# Wireless_RIFID_Reader.net
KiCad netlist of a schematic drawn in EAGLE
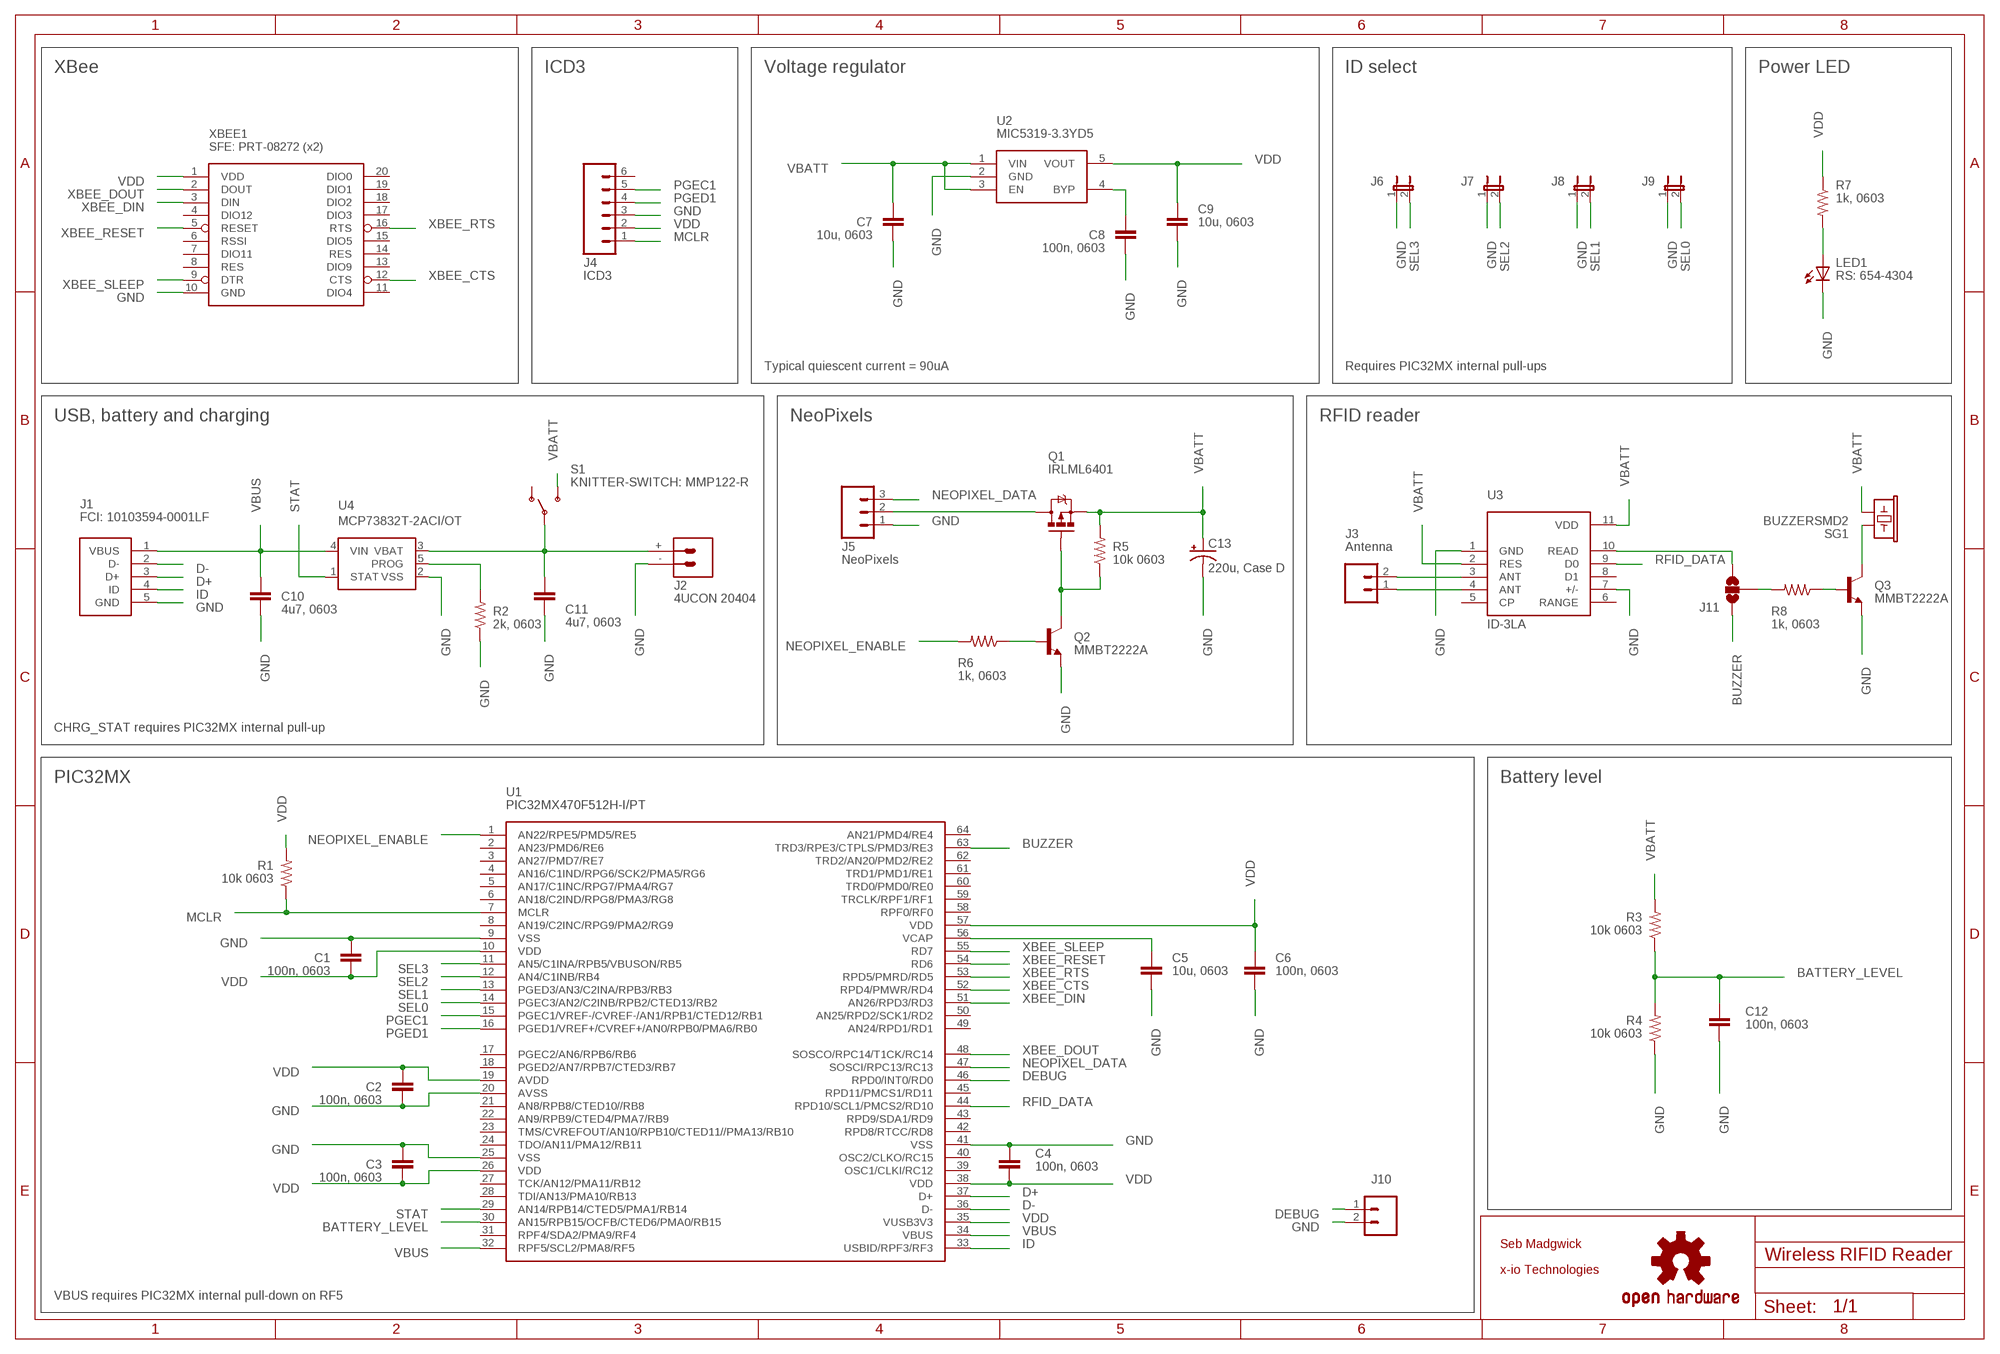
[diagram p0: schematic, sheet 1]

(export (version "E")
  (design (tool "Eeschema 10.0.6"))
  (components
    (comp (ref "C1")
      (value "100n, 0603")
      (footprint "eagle-import:0402-CAP")
      (libsource (lib "eagle-import") (part "CAP0402-CAP"))
    )
    (comp (ref "C2")
      (value "100n, 0603")
      (footprint "eagle-import:0402-CAP")
      (libsource (lib "eagle-import") (part "CAP0402-CAP"))
    )
    (comp (ref "C3")
      (value "100n, 0603")
      (footprint "eagle-import:0402-CAP")
      (libsource (lib "eagle-import") (part "CAP0402-CAP"))
    )
    (comp (ref "C4")
      (value "100n, 0603")
      (footprint "eagle-import:0402-CAP")
      (libsource (lib "eagle-import") (part "CAP0402-CAP"))
    )
    (comp (ref "C5")
      (value "10u, 0603")
      (footprint "eagle-import:0402-CAP")
      (libsource (lib "eagle-import") (part "CAP0402-CAP"))
    )
    (comp (ref "C6")
      (value "100n, 0603")
      (footprint "eagle-import:0402-CAP")
      (libsource (lib "eagle-import") (part "CAP0402-CAP"))
    )
    (comp (ref "C7")
      (value "10u, 0603")
      (footprint "eagle-import:0402-CAP")
      (libsource (lib "eagle-import") (part "CAP0402-CAP"))
    )
    (comp (ref "C8")
      (value "100n, 0603")
      (footprint "eagle-import:0402-CAP")
      (libsource (lib "eagle-import") (part "CAP0402-CAP"))
    )
    (comp (ref "C9")
      (value "10u, 0603")
      (footprint "eagle-import:0402-CAP")
      (libsource (lib "eagle-import") (part "CAP0402-CAP"))
    )
    (comp (ref "C10")
      (value "4u7, 0603")
      (footprint "eagle-import:0402-CAP")
      (libsource (lib "eagle-import") (part "CAP0402-CAP"))
    )
    (comp (ref "C11")
      (value "4u7, 0603")
      (footprint "eagle-import:0402-CAP")
      (libsource (lib "eagle-import") (part "CAP0402-CAP"))
    )
    (comp (ref "C12")
      (value "100n, 0603")
      (footprint "eagle-import:0402-CAP")
      (libsource (lib "eagle-import") (part "CAP0402-CAP"))
    )
    (comp (ref "C13")
      (value "220u, Case D")
      (footprint "eagle-import:SMC_D")
      (libsource (lib "eagle-import") (part "CPOL-USSMCD"))
    )
    (comp (ref "J1")
      (value "FCI: 10103594-0001LF")
      (footprint "eagle-import:10103594-0001LF")
      (libsource (lib "eagle-import") (part "USB-MICRO-B"))
    )
    (comp (ref "J2")
      (value "4UCON 20404")
      (footprint "eagle-import:JST-R_A")
      (libsource (lib "eagle-import") (part "JST"))
    )
    (comp (ref "J3")
      (value "Antenna")
      (footprint "eagle-import:1X02")
      (libsource (lib "eagle-import") (part "SparkFun-Connectors_M02PTH"))
    )
    (comp (ref "J4")
      (value "ICD3")
      (footprint "eagle-import:1X06_NO_SILK")
      (libsource (lib "eagle-import") (part "M06NO_SILK"))
    )
    (comp (ref "J5")
      (value "NeoPixels")
      (footprint "eagle-import:1X03")
      (libsource (lib "eagle-import") (part "M03PTH"))
    )
    (comp (ref "J6")
      (value "JUMPER-2SMD-NO")
      (footprint "eagle-import:SJ_2S-NO")
      (libsource (lib "eagle-import") (part "JUMPER-2SMD-NO"))
    )
    (comp (ref "J7")
      (value "JUMPER-2SMD-NO")
      (footprint "eagle-import:SJ_2S-NO")
      (libsource (lib "eagle-import") (part "JUMPER-2SMD-NO"))
    )
    (comp (ref "J8")
      (value "JUMPER-2SMD-NO")
      (footprint "eagle-import:SJ_2S-NO")
      (libsource (lib "eagle-import") (part "JUMPER-2SMD-NO"))
    )
    (comp (ref "J9")
      (value "JUMPER-2SMD-NO")
      (footprint "eagle-import:SJ_2S-NO")
      (libsource (lib "eagle-import") (part "JUMPER-2SMD-NO"))
    )
    (comp (ref "J10")
      (value "M02PTH")
      (footprint "eagle-import:1X02")
      (libsource (lib "eagle-import") (part "M02PTH"))
    )
    (comp (ref "J11")
      (value "JUMPER-PAD-3-NOFULL_BOX_SILK")
      (footprint "eagle-import:PAD-JUMPER-3-NO_YES_SILK_FULL_BOX")
      (libsource (lib "eagle-import") (part "JUMPER-PAD-3-NOFULL_BOX_SILK"))
    )
    (comp (ref "LED1")
      (value "RS: 654-4304")
      (footprint "eagle-import:LED-0603")
      (libsource (lib "eagle-import") (part "LED0603"))
    )
    (comp (ref "LOGO1")
      (value "OSHW-LOGOM")
      (footprint "eagle-import:OSHW-LOGO-M")
      (libsource (lib "eagle-import") (part "OSHW-LOGOM"))
    )
    (comp (ref "Q1")
      (value "IRLML6401")
      (footprint "eagle-import:SOT23")
      (libsource (lib "eagle-import") (part "MOSFET-PCHANNEL"))
    )
    (comp (ref "Q2")
      (value "MMBT2222A")
      (footprint "eagle-import:SOT23-3")
      (libsource (lib "eagle-import") (part "TRANSISTOR_NPNMMBT2222A"))
    )
    (comp (ref "Q3")
      (value "MMBT2222A")
      (footprint "eagle-import:SOT23-3")
      (libsource (lib "eagle-import") (part "TRANSISTOR_NPNMMBT2222A"))
    )
    (comp (ref "R1")
      (value "10k 0603")
      (footprint "eagle-import:0402-RES")
      (libsource (lib "eagle-import") (part "RESISTOR0402-RES"))
    )
    (comp (ref "R2")
      (value "2k, 0603")
      (footprint "eagle-import:0402-RES")
      (libsource (lib "eagle-import") (part "RESISTOR0402-RES"))
    )
    (comp (ref "R3")
      (value "10k 0603")
      (footprint "eagle-import:0402-RES")
      (libsource (lib "eagle-import") (part "RESISTOR0402-RES"))
    )
    (comp (ref "R4")
      (value "10k 0603")
      (footprint "eagle-import:0402-RES")
      (libsource (lib "eagle-import") (part "RESISTOR0402-RES"))
    )
    (comp (ref "R5")
      (value "10k 0603")
      (footprint "eagle-import:0402-RES")
      (libsource (lib "eagle-import") (part "RESISTOR0402-RES"))
    )
    (comp (ref "R6")
      (value "1k, 0603")
      (footprint "eagle-import:0402-RES")
      (libsource (lib "eagle-import") (part "RESISTOR0402-RES"))
    )
    (comp (ref "R7")
      (value "1k, 0603")
      (footprint "eagle-import:0402-RES")
      (libsource (lib "eagle-import") (part "RESISTOR0402-RES"))
    )
    (comp (ref "R8")
      (value "1k, 0603")
      (footprint "eagle-import:0402-RES")
      (libsource (lib "eagle-import") (part "RESISTOR0402-RES"))
    )
    (comp (ref "S1")
      (value "KNITTER-SWITCH: MMP122-R")
      (footprint "eagle-import:MMP122-R")
      (libsource (lib "eagle-import") (part "SWITCH-DPSTMMP122-R"))
    )
    (comp (ref "SG1")
      (value "BUZZERSMD2")
      (footprint "eagle-import:BUZZER-CCV")
      (libsource (lib "eagle-import") (part "BUZZERSMD2"))
    )
    (comp (ref "U1")
      (value "PIC32MX470F512H-I/PT")
      (footprint "eagle-import:TQFP64-10X10")
      (libsource (lib "eagle-import") (part "PIC32MX470F512H-I/PT"))
    )
    (comp (ref "U2")
      (value "MIC5319-3.3YD5")
      (footprint "eagle-import:SOT23-5")
      (libsource (lib "eagle-import") (part "MIC5319"))
    )
    (comp (ref "U3")
      (value "ID-3LA")
      (footprint "eagle-import:ID-3LA")
      (libsource (lib "eagle-import") (part "ID-3LA"))
    )
    (comp (ref "U4")
      (value "MCP73832T-2ACI/OT")
      (footprint "eagle-import:SOT23-5")
      (libsource (lib "eagle-import") (part "MCP73831"))
    )
    (comp (ref "XBEE1")
      (value "SFE: PRT-08272 (x2)")
      (footprint "eagle-import:XBEE-1")
      (libsource (lib "eagle-import") (part "XBEE-1B1"))
    )
  )
  (nets
    (net (code "1") (name "/BATTERY_LEVEL") (class "Default")
      (node (ref "C12") (pin "1") (pinfunction "1_1") (pintype "passive"))
      (node (ref "R3") (pin "1") (pinfunction "1_1") (pintype "passive"))
      (node (ref "R4") (pin "2") (pinfunction "2_2") (pintype "passive"))
      (node (ref "U1") (pin "30") (pinfunction "AN15/RPB15/OCFB/CTED6/PMA0/RB15_30") (pintype "bidirectional"))
    )
    (net (code "2") (name "/BUZZER") (class "Default")
      (node (ref "J11") (pin "1") (pinfunction "1_1") (pintype "passive"))
      (node (ref "U1") (pin "63") (pinfunction "TRD3/RPE3/CTPLS/PMD3/RE3_63") (pintype "bidirectional"))
    )
    (net (code "3") (name "/D+") (class "Default")
      (node (ref "J1") (pin "3") (pinfunction "D+_3") (pintype "bidirectional"))
      (node (ref "U1") (pin "37") (pinfunction "D+_37") (pintype "bidirectional"))
    )
    (net (code "4") (name "/D-") (class "Default")
      (node (ref "J1") (pin "2") (pinfunction "D-_2") (pintype "bidirectional"))
      (node (ref "U1") (pin "36") (pinfunction "D-_36") (pintype "bidirectional"))
    )
    (net (code "5") (name "/DEBUG") (class "Default")
      (node (ref "J10") (pin "1") (pinfunction "1_1") (pintype "passive"))
      (node (ref "U1") (pin "46") (pinfunction "RPD0/INT0/RD0_46") (pintype "bidirectional"))
    )
    (net (code "6") (name "/GND") (class "Default")
      (node (ref "C1") (pin "1") (pinfunction "1_1") (pintype "passive"))
      (node (ref "C10") (pin "2") (pinfunction "2_2") (pintype "passive"))
      (node (ref "C11") (pin "2") (pinfunction "2_2") (pintype "passive"))
      (node (ref "C12") (pin "2") (pinfunction "2_2") (pintype "passive"))
      (node (ref "C13") (pin "-") (pinfunction "-_-") (pintype "passive"))
      (node (ref "C2") (pin "2") (pinfunction "2_2") (pintype "passive"))
      (node (ref "C3") (pin "1") (pinfunction "1_1") (pintype "passive"))
      (node (ref "C4") (pin "1") (pinfunction "1_1") (pintype "passive"))
      (node (ref "C5") (pin "2") (pinfunction "2_2") (pintype "passive"))
      (node (ref "C6") (pin "2") (pinfunction "2_2") (pintype "passive"))
      (node (ref "C7") (pin "2") (pinfunction "2_2") (pintype "passive"))
      (node (ref "C8") (pin "2") (pinfunction "2_2") (pintype "passive"))
      (node (ref "C9") (pin "2") (pinfunction "2_2") (pintype "passive"))
      (node (ref "J1") (pin "5") (pinfunction "GND_5") (pintype "bidirectional"))
      (node (ref "J10") (pin "2") (pinfunction "2_2") (pintype "passive"))
      (node (ref "J2") (pin "-") (pintype "bidirectional"))
      (node (ref "J4") (pin "3") (pinfunction "3_3") (pintype "passive"))
      (node (ref "J5") (pin "1") (pinfunction "1_1") (pintype "passive"))
      (node (ref "J6") (pin "1") (pinfunction "1_1") (pintype "passive"))
      (node (ref "J7") (pin "1") (pinfunction "1_1") (pintype "passive"))
      (node (ref "J8") (pin "1") (pinfunction "1_1") (pintype "passive"))
      (node (ref "J9") (pin "1") (pinfunction "1_1") (pintype "passive"))
      (node (ref "LED1") (pin "C") (pinfunction "C_C") (pintype "passive"))
      (node (ref "Q2") (pin "2") (pinfunction "E_2") (pintype "passive"))
      (node (ref "Q3") (pin "2") (pinfunction "E_2") (pintype "passive"))
      (node (ref "R2") (pin "1") (pinfunction "1_1") (pintype "passive"))
      (node (ref "R4") (pin "1") (pinfunction "1_1") (pintype "passive"))
      (node (ref "U1") (pin "20") (pinfunction "AVSS_20") (pintype "bidirectional"))
      (node (ref "U1") (pin "25") (pinfunction "VSS_25") (pintype "bidirectional"))
      (node (ref "U1") (pin "41") (pinfunction "VSS_41") (pintype "bidirectional"))
      (node (ref "U1") (pin "9") (pinfunction "VSS_9") (pintype "bidirectional"))
      (node (ref "U2") (pin "2") (pinfunction "GND_2") (pintype "bidirectional"))
      (node (ref "U3") (pin "1") (pinfunction "GND_1") (pintype "bidirectional"))
      (node (ref "U3") (pin "7") (pinfunction "+/-_7") (pintype "bidirectional"))
      (node (ref "U4") (pin "2") (pinfunction "VSS_2") (pintype "power_in"))
      (node (ref "XBEE1") (pin "10") (pinfunction "GND_10") (pintype "power_in"))
    )
    (net (code "7") (name "/ID") (class "Default")
      (node (ref "J1") (pin "4") (pinfunction "ID_4") (pintype "bidirectional"))
      (node (ref "U1") (pin "33") (pinfunction "USBID/RPF3/RF3_33") (pintype "bidirectional"))
    )
    (net (code "8") (name "/MCLR") (class "Default")
      (node (ref "J4") (pin "1") (pinfunction "1_1") (pintype "passive"))
      (node (ref "R1") (pin "1") (pinfunction "1_1") (pintype "passive"))
      (node (ref "U1") (pin "7") (pinfunction "MCLR_7") (pintype "bidirectional"))
    )
    (net (code "9") (name "/NEOPIXEL_DATA") (class "Default")
      (node (ref "J5") (pin "3") (pinfunction "3_3") (pintype "passive"))
      (node (ref "U1") (pin "47") (pinfunction "SOSCI/RPC13/RC13_47") (pintype "bidirectional"))
    )
    (net (code "10") (name "/NEOPIXEL_ENABLE") (class "Default")
      (node (ref "R6") (pin "2") (pinfunction "2_2") (pintype "passive"))
      (node (ref "U1") (pin "1") (pinfunction "AN22/RPE5/PMD5/RE5_1") (pintype "bidirectional"))
    )
    (net (code "11") (name "/PGEC1") (class "Default")
      (node (ref "J4") (pin "5") (pinfunction "5_5") (pintype "passive"))
      (node (ref "U1") (pin "15") (pinfunction "PGEC1/VREF-/CVREF-/AN1/RPB1/CTED12/RB1_15") (pintype "bidirectional"))
    )
    (net (code "12") (name "/PGED1") (class "Default")
      (node (ref "J4") (pin "4") (pinfunction "4_4") (pintype "passive"))
      (node (ref "U1") (pin "16") (pinfunction "PGED1/VREF+/CVREF+/AN0/RPB0/PMA6/RB0_16") (pintype "bidirectional"))
    )
    (net (code "13") (name "/RFID_DATA") (class "Default")
      (node (ref "U1") (pin "44") (pinfunction "RPD10/SCL1/PMCS2/RD10_44") (pintype "bidirectional"))
      (node (ref "U3") (pin "9") (pinfunction "D0_9") (pintype "bidirectional"))
    )
    (net (code "14") (name "/SEL0") (class "Default")
      (node (ref "J9") (pin "2") (pinfunction "2_2") (pintype "passive"))
      (node (ref "U1") (pin "14") (pinfunction "PGEC3/AN2/C2INB/RPB2/CTED13/RB2_14") (pintype "bidirectional"))
    )
    (net (code "15") (name "/SEL1") (class "Default")
      (node (ref "J8") (pin "2") (pinfunction "2_2") (pintype "passive"))
      (node (ref "U1") (pin "13") (pinfunction "PGED3/AN3/C2INA/RPB3/RB3_13") (pintype "bidirectional"))
    )
    (net (code "16") (name "/SEL2") (class "Default")
      (node (ref "J7") (pin "2") (pinfunction "2_2") (pintype "passive"))
      (node (ref "U1") (pin "12") (pinfunction "AN4/C1INB/RB4_12") (pintype "bidirectional"))
    )
    (net (code "17") (name "/SEL3") (class "Default")
      (node (ref "J6") (pin "2") (pinfunction "2_2") (pintype "passive"))
      (node (ref "U1") (pin "11") (pinfunction "AN5/C1INA/RPB5/VBUSON/RB5_11") (pintype "bidirectional"))
    )
    (net (code "18") (name "/STAT") (class "Default")
      (node (ref "U1") (pin "29") (pinfunction "AN14/RPB14/CTED5/PMA1/RB14_29") (pintype "bidirectional"))
      (node (ref "U4") (pin "1") (pinfunction "STAT_1") (pintype "output"))
    )
    (net (code "19") (name "/VBATT") (class "Default")
      (node (ref "C13") (pin "+") (pinfunction "+_+") (pintype "passive"))
      (node (ref "C7") (pin "1") (pinfunction "1_1") (pintype "passive"))
      (node (ref "Q1") (pin "2") (pinfunction "S_2") (pintype "passive"))
      (node (ref "R3") (pin "2") (pinfunction "2_2") (pintype "passive"))
      (node (ref "R5") (pin "2") (pinfunction "2_2") (pintype "passive"))
      (node (ref "S1") (pin "3") (pinfunction "3_3") (pintype "passive"))
      (node (ref "SG1") (pin "-") (pinfunction "2_-") (pintype "passive"))
      (node (ref "U2") (pin "1") (pinfunction "VIN_1") (pintype "bidirectional"))
      (node (ref "U2") (pin "3") (pinfunction "EN_3") (pintype "bidirectional"))
      (node (ref "U3") (pin "11") (pinfunction "VDD_11") (pintype "bidirectional"))
      (node (ref "U3") (pin "2") (pinfunction "RES_2") (pintype "bidirectional"))
    )
    (net (code "20") (name "/VBUS") (class "Default")
      (node (ref "C10") (pin "1") (pinfunction "1_1") (pintype "passive"))
      (node (ref "J1") (pin "1") (pinfunction "VBUS_1") (pintype "bidirectional"))
      (node (ref "U1") (pin "32") (pinfunction "RPF5/SCL2/PMA8/RF5_32") (pintype "bidirectional"))
      (node (ref "U1") (pin "34") (pinfunction "VBUS_34") (pintype "bidirectional"))
      (node (ref "U4") (pin "4") (pinfunction "VIN_4") (pintype "power_in"))
    )
    (net (code "21") (name "/VDD") (class "Default")
      (node (ref "C1") (pin "2") (pinfunction "2_2") (pintype "passive"))
      (node (ref "C2") (pin "1") (pinfunction "1_1") (pintype "passive"))
      (node (ref "C3") (pin "2") (pinfunction "2_2") (pintype "passive"))
      (node (ref "C4") (pin "2") (pinfunction "2_2") (pintype "passive"))
      (node (ref "C6") (pin "1") (pinfunction "1_1") (pintype "passive"))
      (node (ref "C9") (pin "1") (pinfunction "1_1") (pintype "passive"))
      (node (ref "J4") (pin "2") (pinfunction "2_2") (pintype "passive"))
      (node (ref "R1") (pin "2") (pinfunction "2_2") (pintype "passive"))
      (node (ref "R7") (pin "1") (pinfunction "1_1") (pintype "passive"))
      (node (ref "U1") (pin "10") (pinfunction "VDD_10") (pintype "bidirectional"))
      (node (ref "U1") (pin "19") (pinfunction "AVDD_19") (pintype "bidirectional"))
      (node (ref "U1") (pin "26") (pinfunction "VDD_26") (pintype "bidirectional"))
      (node (ref "U1") (pin "35") (pinfunction "VUSB3V3_35") (pintype "bidirectional"))
      (node (ref "U1") (pin "38") (pinfunction "VDD_38") (pintype "bidirectional"))
      (node (ref "U1") (pin "57") (pinfunction "VDD_57") (pintype "bidirectional"))
      (node (ref "U2") (pin "5") (pinfunction "VOUT_5") (pintype "bidirectional"))
      (node (ref "XBEE1") (pin "1") (pinfunction "VDD_1") (pintype "power_in"))
    )
    (net (code "22") (name "/XBEE_CTS") (class "Default")
      (node (ref "U1") (pin "52") (pinfunction "RPD4/PMWR/RD4_52") (pintype "bidirectional"))
      (node (ref "XBEE1") (pin "12") (pinfunction "CTS_12") (pintype "output"))
    )
    (net (code "23") (name "/XBEE_DIN") (class "Default")
      (node (ref "U1") (pin "51") (pinfunction "AN26/RPD3/RD3_51") (pintype "bidirectional"))
      (node (ref "XBEE1") (pin "3") (pinfunction "DIN_3") (pintype "input"))
    )
    (net (code "24") (name "/XBEE_DOUT") (class "Default")
      (node (ref "U1") (pin "48") (pinfunction "SOSCO/RPC14/T1CK/RC14_48") (pintype "bidirectional"))
      (node (ref "XBEE1") (pin "2") (pinfunction "DOUT_2") (pintype "output"))
    )
    (net (code "25") (name "/XBEE_RESET") (class "Default")
      (node (ref "U1") (pin "54") (pinfunction "RD6_54") (pintype "bidirectional"))
      (node (ref "XBEE1") (pin "5") (pinfunction "RESET_5") (pintype "input"))
    )
    (net (code "26") (name "/XBEE_RTS") (class "Default")
      (node (ref "U1") (pin "53") (pinfunction "RPD5/PMRD/RD5_53") (pintype "bidirectional"))
      (node (ref "XBEE1") (pin "16") (pinfunction "RTS_16") (pintype "input"))
    )
    (net (code "27") (name "/XBEE_SLEEP") (class "Default")
      (node (ref "U1") (pin "55") (pinfunction "RD7_55") (pintype "bidirectional"))
      (node (ref "XBEE1") (pin "9") (pinfunction "DTR_9") (pintype "bidirectional"))
    )
    (net (code "28") (name "Net-(J3-Pad1)") (class "Default")
      (node (ref "J3") (pin "1") (pinfunction "1_1") (pintype "passive"))
      (node (ref "U3") (pin "4") (pinfunction "ANT_4") (pintype "bidirectional"))
    )
    (net (code "29") (name "Net-(J3-Pad2)") (class "Default")
      (node (ref "J3") (pin "2") (pinfunction "2_2") (pintype "passive"))
      (node (ref "U3") (pin "3") (pinfunction "ANT_3") (pintype "bidirectional"))
    )
    (net (code "30") (name "Net-(J11-Pad2)") (class "Default")
      (node (ref "J11") (pin "2") (pinfunction "2_2") (pintype "passive"))
      (node (ref "R8") (pin "2") (pinfunction "2_2") (pintype "passive"))
    )
    (net (code "31") (name "Net-(LED1-PadA)") (class "Default")
      (node (ref "LED1") (pin "A") (pinfunction "A_A") (pintype "passive"))
      (node (ref "R7") (pin "2") (pinfunction "2_2") (pintype "passive"))
    )
    (net (code "32") (name "Net-(Q1-D)") (class "Default")
      (node (ref "J5") (pin "2") (pinfunction "2_2") (pintype "passive"))
      (node (ref "Q1") (pin "3") (pinfunction "D_3") (pintype "passive"))
    )
    (net (code "33") (name "Net-(Q1-G)") (class "Default")
      (node (ref "Q1") (pin "1") (pinfunction "G_1") (pintype "passive"))
      (node (ref "Q2") (pin "3") (pinfunction "C_3") (pintype "passive"))
      (node (ref "R5") (pin "1") (pinfunction "1_1") (pintype "passive"))
    )
    (net (code "34") (name "Net-(Q2-B)") (class "Default")
      (node (ref "Q2") (pin "1") (pinfunction "B_1") (pintype "passive"))
      (node (ref "R6") (pin "1") (pinfunction "1_1") (pintype "passive"))
    )
    (net (code "35") (name "Net-(Q3-B)") (class "Default")
      (node (ref "Q3") (pin "1") (pinfunction "B_1") (pintype "passive"))
      (node (ref "R8") (pin "1") (pinfunction "1_1") (pintype "passive"))
    )
    (net (code "36") (name "Net-(Q3-C)") (class "Default")
      (node (ref "Q3") (pin "3") (pinfunction "C_3") (pintype "passive"))
      (node (ref "SG1") (pin "+") (pinfunction "1_+") (pintype "passive"))
    )
    (net (code "37") (name "Net-(U1-VCAP)") (class "Default")
      (node (ref "C5") (pin "1") (pinfunction "1_1") (pintype "passive"))
      (node (ref "U1") (pin "56") (pinfunction "VCAP_56") (pintype "bidirectional"))
    )
    (net (code "38") (name "Net-(U2-BYP)") (class "Default")
      (node (ref "C8") (pin "1") (pinfunction "1_1") (pintype "passive"))
      (node (ref "U2") (pin "4") (pinfunction "BYP_4") (pintype "bidirectional"))
    )
    (net (code "39") (name "Net-(U3-READ)") (class "Default")
      (node (ref "J11") (pin "3") (pinfunction "3_3") (pintype "passive"))
      (node (ref "U3") (pin "10") (pinfunction "READ_10") (pintype "bidirectional"))
    )
    (net (code "40") (name "Net-(U4-PROG)") (class "Default")
      (node (ref "R2") (pin "2") (pinfunction "2_2") (pintype "passive"))
      (node (ref "U4") (pin "5") (pinfunction "PROG_5") (pintype "input"))
    )
    (net (code "41") (name "Net-(U4-VBAT)") (class "Default")
      (node (ref "C11") (pin "1") (pinfunction "1_1") (pintype "passive"))
      (node (ref "J2") (pin "+") (pintype "bidirectional"))
      (node (ref "S1") (pin "2") (pinfunction "2_2") (pintype "passive"))
      (node (ref "U4") (pin "3") (pinfunction "VBAT_3") (pintype "power_in"))
    )
    (net (code "42") (name "unconnected-(J4-Pad6)") (class "Default")
      (node (ref "J4") (pin "6") (pinfunction "6_6") (pintype "passive"))
    )
    (net (code "43") (name "unconnected-(S1-Pad1)") (class "Default")
      (node (ref "S1") (pin "1") (pinfunction "1_1") (pintype "passive"))
    )
    (net (code "44") (name "unconnected-(U1-AN8{slash}RPB8{slash}CTED10{slash}{slash}RB8-Pad21)") (class "Default")
      (node (ref "U1") (pin "21") (pinfunction "AN8/RPB8/CTED10//RB8_21") (pintype "bidirectional"))
    )
    (net (code "45") (name "unconnected-(U1-AN9{slash}RPB9{slash}CTED4{slash}PMA7{slash}RB9-Pad22)") (class "Default")
      (node (ref "U1") (pin "22") (pinfunction "AN9/RPB9/CTED4/PMA7/RB9_22") (pintype "bidirectional"))
    )
    (net (code "46") (name "unconnected-(U1-AN16{slash}C1IND{slash}RPG6{slash}SCK2{slash}PMA5{slash}RG6-Pad4)") (class "Default")
      (node (ref "U1") (pin "4") (pinfunction "AN16/C1IND/RPG6/SCK2/PMA5/RG6_4") (pintype "bidirectional"))
    )
    (net (code "47") (name "unconnected-(U1-AN17{slash}C1INC{slash}RPG7{slash}PMA4{slash}RG7-Pad5)") (class "Default")
      (node (ref "U1") (pin "5") (pinfunction "AN17/C1INC/RPG7/PMA4/RG7_5") (pintype "bidirectional"))
    )
    (net (code "48") (name "unconnected-(U1-AN18{slash}C2IND{slash}RPG8{slash}PMA3{slash}RG8-Pad6)") (class "Default")
      (node (ref "U1") (pin "6") (pinfunction "AN18/C2IND/RPG8/PMA3/RG8_6") (pintype "bidirectional"))
    )
    (net (code "49") (name "unconnected-(U1-AN19{slash}C2INC{slash}RPG9{slash}PMA2{slash}RG9-Pad8)") (class "Default")
      (node (ref "U1") (pin "8") (pinfunction "AN19/C2INC/RPG9/PMA2/RG9_8") (pintype "bidirectional"))
    )
    (net (code "50") (name "unconnected-(U1-AN21{slash}PMD4{slash}RE4-Pad64)") (class "Default")
      (node (ref "U1") (pin "64") (pinfunction "AN21/PMD4/RE4_64") (pintype "bidirectional"))
    )
    (net (code "51") (name "unconnected-(U1-AN23{slash}PMD6{slash}RE6-Pad2)") (class "Default")
      (node (ref "U1") (pin "2") (pinfunction "AN23/PMD6/RE6_2") (pintype "bidirectional"))
    )
    (net (code "52") (name "unconnected-(U1-AN24{slash}RPD1{slash}RD1-Pad49)") (class "Default")
      (node (ref "U1") (pin "49") (pinfunction "AN24/RPD1/RD1_49") (pintype "bidirectional"))
    )
    (net (code "53") (name "unconnected-(U1-AN25{slash}RPD2{slash}SCK1{slash}RD2-Pad50)") (class "Default")
      (node (ref "U1") (pin "50") (pinfunction "AN25/RPD2/SCK1/RD2_50") (pintype "bidirectional"))
    )
    (net (code "54") (name "unconnected-(U1-AN27{slash}PMD7{slash}RE7-Pad3)") (class "Default")
      (node (ref "U1") (pin "3") (pinfunction "AN27/PMD7/RE7_3") (pintype "bidirectional"))
    )
    (net (code "55") (name "unconnected-(U1-OSC1{slash}CLKI{slash}RC12-Pad39)") (class "Default")
      (node (ref "U1") (pin "39") (pinfunction "OSC1/CLKI/RC12_39") (pintype "bidirectional"))
    )
    (net (code "56") (name "unconnected-(U1-OSC2{slash}CLKO{slash}RC15-Pad40)") (class "Default")
      (node (ref "U1") (pin "40") (pinfunction "OSC2/CLKO/RC15_40") (pintype "bidirectional"))
    )
    (net (code "57") (name "unconnected-(U1-PGEC2{slash}AN6{slash}RPB6{slash}RB6-Pad17)") (class "Default")
      (node (ref "U1") (pin "17") (pinfunction "PGEC2/AN6/RPB6/RB6_17") (pintype "bidirectional"))
    )
    (net (code "58") (name "unconnected-(U1-PGED2{slash}AN7{slash}RPB7{slash}CTED3{slash}RB7-Pad18)") (class "Default")
      (node (ref "U1") (pin "18") (pinfunction "PGED2/AN7/RPB7/CTED3/RB7_18") (pintype "bidirectional"))
    )
    (net (code "59") (name "unconnected-(U1-RPD8{slash}RTCC{slash}RD8-Pad42)") (class "Default")
      (node (ref "U1") (pin "42") (pinfunction "RPD8/RTCC/RD8_42") (pintype "bidirectional"))
    )
    (net (code "60") (name "unconnected-(U1-RPD9{slash}SDA1{slash}RD9-Pad43)") (class "Default")
      (node (ref "U1") (pin "43") (pinfunction "RPD9/SDA1/RD9_43") (pintype "bidirectional"))
    )
    (net (code "61") (name "unconnected-(U1-RPD11{slash}PMCS1{slash}RD11-Pad45)") (class "Default")
      (node (ref "U1") (pin "45") (pinfunction "RPD11/PMCS1/RD11_45") (pintype "bidirectional"))
    )
    (net (code "62") (name "unconnected-(U1-RPF0{slash}RF0-Pad58)") (class "Default")
      (node (ref "U1") (pin "58") (pinfunction "RPF0/RF0_58") (pintype "bidirectional"))
    )
    (net (code "63") (name "unconnected-(U1-RPF4{slash}SDA2{slash}PMA9{slash}RF4-Pad31)") (class "Default")
      (node (ref "U1") (pin "31") (pinfunction "RPF4/SDA2/PMA9/RF4_31") (pintype "bidirectional"))
    )
    (net (code "64") (name "unconnected-(U1-TCK{slash}AN12{slash}PMA11{slash}RB12-Pad27)") (class "Default")
      (node (ref "U1") (pin "27") (pinfunction "TCK/AN12/PMA11/RB12_27") (pintype "bidirectional"))
    )
    (net (code "65") (name "unconnected-(U1-TDI{slash}AN13{slash}PMA10{slash}RB13-Pad28)") (class "Default")
      (node (ref "U1") (pin "28") (pinfunction "TDI/AN13/PMA10/RB13_28") (pintype "bidirectional"))
    )
    (net (code "66") (name "unconnected-(U1-TDO{slash}AN11{slash}PMA12{slash}RB11-Pad24)") (class "Default")
      (node (ref "U1") (pin "24") (pinfunction "TDO/AN11/PMA12/RB11_24") (pintype "bidirectional"))
    )
    (net (code "67") (name "unconnected-(U1-TMS{slash}CVREFOUT{slash}AN10{slash}RPB10{slash}CTED11{slash}{slash}PMA13{slash}RB10-Pad23)") (class "Default")
      (node (ref "U1") (pin "23") (pinfunction "TMS/CVREFOUT/AN10/RPB10/CTED11//PMA13/RB10_23") (pintype "bidirectional"))
    )
    (net (code "68") (name "unconnected-(U1-TRCLK{slash}RPF1{slash}RF1-Pad59)") (class "Default")
      (node (ref "U1") (pin "59") (pinfunction "TRCLK/RPF1/RF1_59") (pintype "bidirectional"))
    )
    (net (code "69") (name "unconnected-(U1-TRD0{slash}PMD0{slash}RE0-Pad60)") (class "Default")
      (node (ref "U1") (pin "60") (pinfunction "TRD0/PMD0/RE0_60") (pintype "bidirectional"))
    )
    (net (code "70") (name "unconnected-(U1-TRD1{slash}PMD1{slash}RE1-Pad61)") (class "Default")
      (node (ref "U1") (pin "61") (pinfunction "TRD1/PMD1/RE1_61") (pintype "bidirectional"))
    )
    (net (code "71") (name "unconnected-(U1-TRD2{slash}AN20{slash}PMD2{slash}RE2-Pad62)") (class "Default")
      (node (ref "U1") (pin "62") (pinfunction "TRD2/AN20/PMD2/RE2_62") (pintype "bidirectional"))
    )
    (net (code "72") (name "unconnected-(U3-CP-Pad5)") (class "Default")
      (node (ref "U3") (pin "5") (pinfunction "CP_5") (pintype "bidirectional"))
    )
    (net (code "73") (name "unconnected-(U3-D1-Pad8)") (class "Default")
      (node (ref "U3") (pin "8") (pinfunction "D1_8") (pintype "bidirectional"))
    )
    (net (code "74") (name "unconnected-(U3-RANGE-Pad6)") (class "Default")
      (node (ref "U3") (pin "6") (pinfunction "RANGE_6") (pintype "bidirectional"))
    )
    (net (code "75") (name "unconnected-(XBEE1-DIO0-Pad20)") (class "Default")
      (node (ref "XBEE1") (pin "20") (pinfunction "DIO0_20") (pintype "bidirectional"))
    )
    (net (code "76") (name "unconnected-(XBEE1-DIO1-Pad19)") (class "Default")
      (node (ref "XBEE1") (pin "19") (pinfunction "DIO1_19") (pintype "bidirectional"))
    )
    (net (code "77") (name "unconnected-(XBEE1-DIO2-Pad18)") (class "Default")
      (node (ref "XBEE1") (pin "18") (pinfunction "DIO2_18") (pintype "bidirectional"))
    )
    (net (code "78") (name "unconnected-(XBEE1-DIO3-Pad17)") (class "Default")
      (node (ref "XBEE1") (pin "17") (pinfunction "DIO3_17") (pintype "bidirectional"))
    )
    (net (code "79") (name "unconnected-(XBEE1-DIO4-Pad11)") (class "Default")
      (node (ref "XBEE1") (pin "11") (pinfunction "DIO4_11") (pintype "bidirectional"))
    )
    (net (code "80") (name "unconnected-(XBEE1-DIO5-Pad15)") (class "Default")
      (node (ref "XBEE1") (pin "15") (pinfunction "DIO5_15") (pintype "bidirectional"))
    )
    (net (code "81") (name "unconnected-(XBEE1-DIO9-Pad13)") (class "Default")
      (node (ref "XBEE1") (pin "13") (pinfunction "DIO9_13") (pintype "bidirectional"))
    )
    (net (code "82") (name "unconnected-(XBEE1-DIO11-Pad7)") (class "Default")
      (node (ref "XBEE1") (pin "7") (pinfunction "DIO11_7") (pintype "bidirectional"))
    )
    (net (code "83") (name "unconnected-(XBEE1-DIO12-Pad4)") (class "Default")
      (node (ref "XBEE1") (pin "4") (pinfunction "DIO12_4") (pintype "bidirectional"))
    )
    (net (code "84") (name "unconnected-(XBEE1-RES-Pad8)") (class "Default")
      (node (ref "XBEE1") (pin "8") (pinfunction "RES_8") (pintype "bidirectional"))
    )
    (net (code "85") (name "unconnected-(XBEE1-RES-Pad14)") (class "Default")
      (node (ref "XBEE1") (pin "14") (pinfunction "RES_14") (pintype "bidirectional"))
    )
    (net (code "86") (name "unconnected-(XBEE1-RSSI-Pad6)") (class "Default")
      (node (ref "XBEE1") (pin "6") (pinfunction "RSSI_6") (pintype "bidirectional"))
    )
  )
)
